# untitled.net
KiCad netlist of a schematic drawn in EAGLE
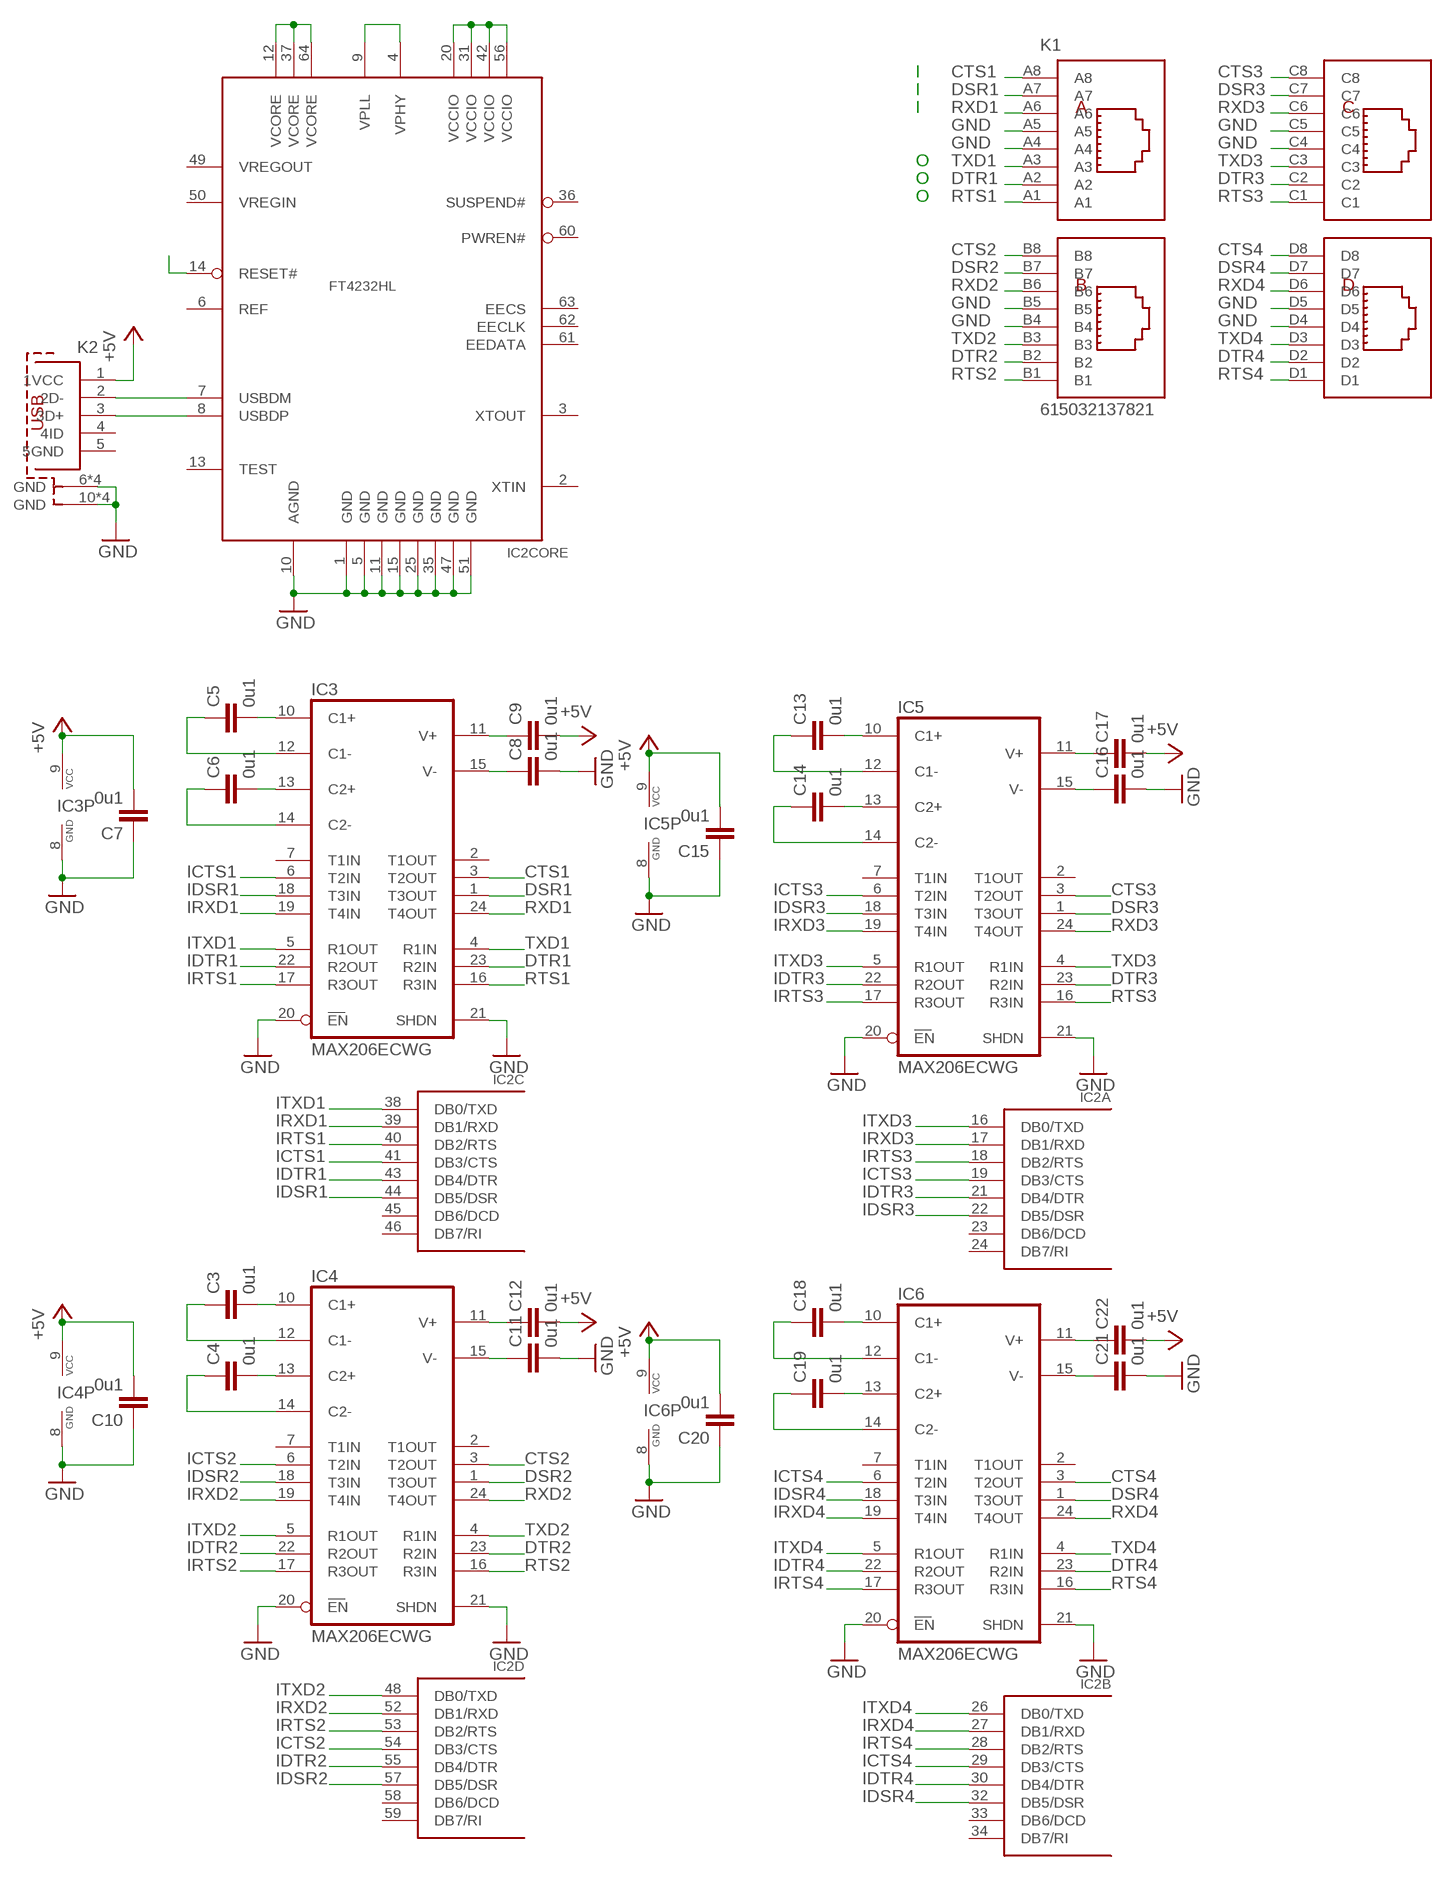
[diagram p0: schematic, sheet 1]

(export (version "E")
  (design (tool "Eeschema 10.0.6"))
  (components
    (comp (ref "C3")
      (value "0u1")
      (footprint "eagle-import:C0603")
      (libsource (lib "eagle-import") (part "C-EUC0603"))
    )
    (comp (ref "C4")
      (value "0u1")
      (footprint "eagle-import:C0603")
      (libsource (lib "eagle-import") (part "C-EUC0603"))
    )
    (comp (ref "C5")
      (value "0u1")
      (footprint "eagle-import:C0603")
      (libsource (lib "eagle-import") (part "C-EUC0603"))
    )
    (comp (ref "C6")
      (value "0u1")
      (footprint "eagle-import:C0603")
      (libsource (lib "eagle-import") (part "C-EUC0603"))
    )
    (comp (ref "C7")
      (value "0u1")
      (footprint "eagle-import:C0603")
      (libsource (lib "eagle-import") (part "C-EUC0603"))
    )
    (comp (ref "C8")
      (value "0u1")
      (footprint "eagle-import:C0603")
      (libsource (lib "eagle-import") (part "C-EUC0603"))
    )
    (comp (ref "C9")
      (value "0u1")
      (footprint "eagle-import:C0603")
      (libsource (lib "eagle-import") (part "C-EUC0603"))
    )
    (comp (ref "C10")
      (value "0u1")
      (footprint "eagle-import:C0603")
      (libsource (lib "eagle-import") (part "C-EUC0603"))
    )
    (comp (ref "C11")
      (value "0u1")
      (footprint "eagle-import:C0603")
      (libsource (lib "eagle-import") (part "C-EUC0603"))
    )
    (comp (ref "C12")
      (value "0u1")
      (footprint "eagle-import:C0603")
      (libsource (lib "eagle-import") (part "C-EUC0603"))
    )
    (comp (ref "C13")
      (value "0u1")
      (footprint "eagle-import:C0603")
      (libsource (lib "eagle-import") (part "C-EUC0603"))
    )
    (comp (ref "C14")
      (value "0u1")
      (footprint "eagle-import:C0603")
      (libsource (lib "eagle-import") (part "C-EUC0603"))
    )
    (comp (ref "C15")
      (value "0u1")
      (footprint "eagle-import:C0603")
      (libsource (lib "eagle-import") (part "C-EUC0603"))
    )
    (comp (ref "C16")
      (value "0u1")
      (footprint "eagle-import:C0603")
      (libsource (lib "eagle-import") (part "C-EUC0603"))
    )
    (comp (ref "C17")
      (value "0u1")
      (footprint "eagle-import:C0603")
      (libsource (lib "eagle-import") (part "C-EUC0603"))
    )
    (comp (ref "C18")
      (value "0u1")
      (footprint "eagle-import:C0603")
      (libsource (lib "eagle-import") (part "C-EUC0603"))
    )
    (comp (ref "C19")
      (value "0u1")
      (footprint "eagle-import:C0603")
      (libsource (lib "eagle-import") (part "C-EUC0603"))
    )
    (comp (ref "C20")
      (value "0u1")
      (footprint "eagle-import:C0603")
      (libsource (lib "eagle-import") (part "C-EUC0603"))
    )
    (comp (ref "C21")
      (value "0u1")
      (footprint "eagle-import:C0603")
      (libsource (lib "eagle-import") (part "C-EUC0603"))
    )
    (comp (ref "C22")
      (value "0u1")
      (footprint "eagle-import:C0603")
      (libsource (lib "eagle-import") (part "C-EUC0603"))
    )
    (comp (ref "IC2")
      (value "FT4232HL")
      (footprint "eagle-import:LQFP64")
      (libsource (lib "eagle-import") (part "FT4232HL"))
    )
    (comp (ref "IC3")
      (value "MAX206ECWG")
      (footprint "eagle-import:SO24L")
      (fields (field (name "MF") "MAXIM") (field (name "MPN") "MAX206ECWG+"))
      (libsource (lib "eagle-import") (part "MAX206ECWG"))
    )
    (comp (ref "IC4")
      (value "MAX206ECWG")
      (footprint "eagle-import:SO24L")
      (fields (field (name "MF") "MAXIM") (field (name "MPN") "MAX206ECWG+"))
      (libsource (lib "eagle-import") (part "MAX206ECWG"))
    )
    (comp (ref "IC5")
      (value "MAX206ECWG")
      (footprint "eagle-import:SO24L")
      (fields (field (name "MF") "MAXIM") (field (name "MPN") "MAX206ECWG+"))
      (libsource (lib "eagle-import") (part "MAX206ECWG"))
    )
    (comp (ref "IC6")
      (value "MAX206ECWG")
      (footprint "eagle-import:SO24L")
      (fields (field (name "MF") "MAXIM") (field (name "MPN") "MAX206ECWG+"))
      (libsource (lib "eagle-import") (part "MAX206ECWG"))
    )
    (comp (ref "K1")
      (value "615032137821")
      (footprint "eagle-import:615032137821")
      (libsource (lib "eagle-import") (part "615032137821"))
    )
    (comp (ref "K2")
      (value "629105150921")
      (footprint "eagle-import:629105150921")
      (libsource (lib "eagle-import") (part "629105150921"))
    )
  )
  (nets
    (net (code "1") (name "+5V") (class "Default")
      (node (ref "C10") (pin "2") (pinfunction "2_2") (pintype "passive"))
      (node (ref "C12") (pin "2") (pinfunction "2_2") (pintype "passive"))
      (node (ref "C15") (pin "2") (pinfunction "2_2") (pintype "passive"))
      (node (ref "C17") (pin "2") (pinfunction "2_2") (pintype "passive"))
      (node (ref "C20") (pin "2") (pinfunction "2_2") (pintype "passive"))
      (node (ref "C22") (pin "2") (pinfunction "2_2") (pintype "passive"))
      (node (ref "C7") (pin "2") (pinfunction "2_2") (pintype "passive"))
      (node (ref "C9") (pin "2") (pinfunction "2_2") (pintype "passive"))
      (node (ref "IC3") (pin "9") (pinfunction "VCC_9") (pintype "power_in"))
      (node (ref "IC4") (pin "9") (pinfunction "VCC_9") (pintype "power_in"))
      (node (ref "IC5") (pin "9") (pinfunction "VCC_9") (pintype "power_in"))
      (node (ref "IC6") (pin "9") (pinfunction "VCC_9") (pintype "power_in"))
      (node (ref "K2") (pin "1") (pinfunction "1VCC_1") (pintype "passive"))
    )
    (net (code "2") (name "/CTS1") (class "Default")
      (node (ref "IC3") (pin "3") (pinfunction "T2OUT_3") (pintype "output"))
      (node (ref "K1") (pin "A8") (pinfunction "A8_A8") (pintype "passive"))
    )
    (net (code "3") (name "/CTS2") (class "Default")
      (node (ref "IC4") (pin "3") (pinfunction "T2OUT_3") (pintype "output"))
      (node (ref "K1") (pin "B8") (pinfunction "B8_B8") (pintype "passive"))
    )
    (net (code "4") (name "/CTS3") (class "Default")
      (node (ref "IC5") (pin "3") (pinfunction "T2OUT_3") (pintype "output"))
      (node (ref "K1") (pin "C8") (pinfunction "C8_C8") (pintype "passive"))
    )
    (net (code "5") (name "/CTS4") (class "Default")
      (node (ref "IC6") (pin "3") (pinfunction "T2OUT_3") (pintype "output"))
      (node (ref "K1") (pin "D8") (pinfunction "D8_D8") (pintype "passive"))
    )
    (net (code "6") (name "/DSR1") (class "Default")
      (node (ref "IC3") (pin "1") (pinfunction "T3OUT_1") (pintype "output"))
      (node (ref "K1") (pin "A7") (pinfunction "A7_A7") (pintype "passive"))
    )
    (net (code "7") (name "/DSR2") (class "Default")
      (node (ref "IC4") (pin "1") (pinfunction "T3OUT_1") (pintype "output"))
      (node (ref "K1") (pin "B7") (pinfunction "B7_B7") (pintype "passive"))
    )
    (net (code "8") (name "/DSR3") (class "Default")
      (node (ref "IC5") (pin "1") (pinfunction "T3OUT_1") (pintype "output"))
      (node (ref "K1") (pin "C7") (pinfunction "C7_C7") (pintype "passive"))
    )
    (net (code "9") (name "/DSR4") (class "Default")
      (node (ref "IC6") (pin "1") (pinfunction "T3OUT_1") (pintype "output"))
      (node (ref "K1") (pin "D7") (pinfunction "D7_D7") (pintype "passive"))
    )
    (net (code "10") (name "/DTR1") (class "Default")
      (node (ref "IC3") (pin "23") (pinfunction "R2IN_23") (pintype "input"))
      (node (ref "K1") (pin "A2") (pinfunction "A2_A2") (pintype "passive"))
    )
    (net (code "11") (name "/DTR2") (class "Default")
      (node (ref "IC4") (pin "23") (pinfunction "R2IN_23") (pintype "input"))
      (node (ref "K1") (pin "B2") (pinfunction "B2_B2") (pintype "passive"))
    )
    (net (code "12") (name "/DTR3") (class "Default")
      (node (ref "IC5") (pin "23") (pinfunction "R2IN_23") (pintype "input"))
      (node (ref "K1") (pin "C2") (pinfunction "C2_C2") (pintype "passive"))
    )
    (net (code "13") (name "/DTR4") (class "Default")
      (node (ref "IC6") (pin "23") (pinfunction "R2IN_23") (pintype "input"))
      (node (ref "K1") (pin "D2") (pinfunction "D2_D2") (pintype "passive"))
    )
    (net (code "14") (name "/ICTS1") (class "Default")
      (node (ref "IC2") (pin "41") (pinfunction "DB3/CTS_41") (pintype "bidirectional"))
      (node (ref "IC3") (pin "6") (pinfunction "T2IN_6") (pintype "input"))
    )
    (net (code "15") (name "/ICTS2") (class "Default")
      (node (ref "IC2") (pin "54") (pinfunction "DB3/CTS_54") (pintype "bidirectional"))
      (node (ref "IC4") (pin "6") (pinfunction "T2IN_6") (pintype "input"))
    )
    (net (code "16") (name "/ICTS3") (class "Default")
      (node (ref "IC2") (pin "19") (pinfunction "DB3/CTS_19") (pintype "bidirectional"))
      (node (ref "IC5") (pin "6") (pinfunction "T2IN_6") (pintype "input"))
    )
    (net (code "17") (name "/ICTS4") (class "Default")
      (node (ref "IC2") (pin "29") (pinfunction "DB3/CTS_29") (pintype "bidirectional"))
      (node (ref "IC6") (pin "6") (pinfunction "T2IN_6") (pintype "input"))
    )
    (net (code "18") (name "/IDSR1") (class "Default")
      (node (ref "IC2") (pin "44") (pinfunction "DB5/DSR_44") (pintype "bidirectional"))
      (node (ref "IC3") (pin "18") (pinfunction "T3IN_18") (pintype "input"))
    )
    (net (code "19") (name "/IDSR2") (class "Default")
      (node (ref "IC2") (pin "57") (pinfunction "DB5/DSR_57") (pintype "bidirectional"))
      (node (ref "IC4") (pin "18") (pinfunction "T3IN_18") (pintype "input"))
    )
    (net (code "20") (name "/IDSR3") (class "Default")
      (node (ref "IC2") (pin "22") (pinfunction "DB5/DSR_22") (pintype "bidirectional"))
      (node (ref "IC5") (pin "18") (pinfunction "T3IN_18") (pintype "input"))
    )
    (net (code "21") (name "/IDSR4") (class "Default")
      (node (ref "IC2") (pin "32") (pinfunction "DB5/DSR_32") (pintype "bidirectional"))
      (node (ref "IC6") (pin "18") (pinfunction "T3IN_18") (pintype "input"))
    )
    (net (code "22") (name "/IDTR1") (class "Default")
      (node (ref "IC2") (pin "43") (pinfunction "DB4/DTR_43") (pintype "bidirectional"))
      (node (ref "IC3") (pin "22") (pinfunction "R2OUT_22") (pintype "output"))
    )
    (net (code "23") (name "/IDTR2") (class "Default")
      (node (ref "IC2") (pin "55") (pinfunction "DB4/DTR_55") (pintype "bidirectional"))
      (node (ref "IC4") (pin "22") (pinfunction "R2OUT_22") (pintype "output"))
    )
    (net (code "24") (name "/IDTR3") (class "Default")
      (node (ref "IC2") (pin "21") (pinfunction "DB4/DTR_21") (pintype "bidirectional"))
      (node (ref "IC5") (pin "22") (pinfunction "R2OUT_22") (pintype "output"))
    )
    (net (code "25") (name "/IDTR4") (class "Default")
      (node (ref "IC2") (pin "30") (pinfunction "DB4/DTR_30") (pintype "bidirectional"))
      (node (ref "IC6") (pin "22") (pinfunction "R2OUT_22") (pintype "output"))
    )
    (net (code "26") (name "/IRTS1") (class "Default")
      (node (ref "IC2") (pin "40") (pinfunction "DB2/RTS_40") (pintype "bidirectional"))
      (node (ref "IC3") (pin "17") (pinfunction "R3OUT_17") (pintype "output"))
    )
    (net (code "27") (name "/IRTS2") (class "Default")
      (node (ref "IC2") (pin "53") (pinfunction "DB2/RTS_53") (pintype "bidirectional"))
      (node (ref "IC4") (pin "17") (pinfunction "R3OUT_17") (pintype "output"))
    )
    (net (code "28") (name "/IRTS3") (class "Default")
      (node (ref "IC2") (pin "18") (pinfunction "DB2/RTS_18") (pintype "bidirectional"))
      (node (ref "IC5") (pin "17") (pinfunction "R3OUT_17") (pintype "output"))
    )
    (net (code "29") (name "/IRTS4") (class "Default")
      (node (ref "IC2") (pin "28") (pinfunction "DB2/RTS_28") (pintype "bidirectional"))
      (node (ref "IC6") (pin "17") (pinfunction "R3OUT_17") (pintype "output"))
    )
    (net (code "30") (name "/IRXD1") (class "Default")
      (node (ref "IC2") (pin "39") (pinfunction "DB1/RXD_39") (pintype "bidirectional"))
      (node (ref "IC3") (pin "19") (pinfunction "T4IN_19") (pintype "input"))
    )
    (net (code "31") (name "/IRXD2") (class "Default")
      (node (ref "IC2") (pin "52") (pinfunction "DB1/RXD_52") (pintype "bidirectional"))
      (node (ref "IC4") (pin "19") (pinfunction "T4IN_19") (pintype "input"))
    )
    (net (code "32") (name "/IRXD3") (class "Default")
      (node (ref "IC2") (pin "17") (pinfunction "DB1/RXD_17") (pintype "bidirectional"))
      (node (ref "IC5") (pin "19") (pinfunction "T4IN_19") (pintype "input"))
    )
    (net (code "33") (name "/IRXD4") (class "Default")
      (node (ref "IC2") (pin "27") (pinfunction "DB1/RXD_27") (pintype "bidirectional"))
      (node (ref "IC6") (pin "19") (pinfunction "T4IN_19") (pintype "input"))
    )
    (net (code "34") (name "/ITXD1") (class "Default")
      (node (ref "IC2") (pin "38") (pinfunction "DB0/TXD_38") (pintype "bidirectional"))
      (node (ref "IC3") (pin "5") (pinfunction "R1OUT_5") (pintype "output"))
    )
    (net (code "35") (name "/ITXD2") (class "Default")
      (node (ref "IC2") (pin "48") (pinfunction "DB0/TXD_48") (pintype "bidirectional"))
      (node (ref "IC4") (pin "5") (pinfunction "R1OUT_5") (pintype "output"))
    )
    (net (code "36") (name "/ITXD3") (class "Default")
      (node (ref "IC2") (pin "16") (pinfunction "DB0/TXD_16") (pintype "bidirectional"))
      (node (ref "IC5") (pin "5") (pinfunction "R1OUT_5") (pintype "output"))
    )
    (net (code "37") (name "/ITXD4") (class "Default")
      (node (ref "IC2") (pin "26") (pinfunction "DB0/TXD_26") (pintype "bidirectional"))
      (node (ref "IC6") (pin "5") (pinfunction "R1OUT_5") (pintype "output"))
    )
    (net (code "38") (name "/RTS1") (class "Default")
      (node (ref "IC3") (pin "16") (pinfunction "R3IN_16") (pintype "input"))
      (node (ref "K1") (pin "A1") (pinfunction "A1_A1") (pintype "passive"))
    )
    (net (code "39") (name "/RTS2") (class "Default")
      (node (ref "IC4") (pin "16") (pinfunction "R3IN_16") (pintype "input"))
      (node (ref "K1") (pin "B1") (pinfunction "B1_B1") (pintype "passive"))
    )
    (net (code "40") (name "/RTS3") (class "Default")
      (node (ref "IC5") (pin "16") (pinfunction "R3IN_16") (pintype "input"))
      (node (ref "K1") (pin "C1") (pinfunction "C1_C1") (pintype "passive"))
    )
    (net (code "41") (name "/RTS4") (class "Default")
      (node (ref "IC6") (pin "16") (pinfunction "R3IN_16") (pintype "input"))
      (node (ref "K1") (pin "D1") (pinfunction "D1_D1") (pintype "passive"))
    )
    (net (code "42") (name "/RXD1") (class "Default")
      (node (ref "IC3") (pin "24") (pinfunction "T4OUT_24") (pintype "output"))
      (node (ref "K1") (pin "A6") (pinfunction "A6_A6") (pintype "passive"))
    )
    (net (code "43") (name "/RXD2") (class "Default")
      (node (ref "IC4") (pin "24") (pinfunction "T4OUT_24") (pintype "output"))
      (node (ref "K1") (pin "B6") (pinfunction "B6_B6") (pintype "passive"))
    )
    (net (code "44") (name "/RXD3") (class "Default")
      (node (ref "IC5") (pin "24") (pinfunction "T4OUT_24") (pintype "output"))
      (node (ref "K1") (pin "C6") (pinfunction "C6_C6") (pintype "passive"))
    )
    (net (code "45") (name "/RXD4") (class "Default")
      (node (ref "IC6") (pin "24") (pinfunction "T4OUT_24") (pintype "output"))
      (node (ref "K1") (pin "D6") (pinfunction "D6_D6") (pintype "passive"))
    )
    (net (code "46") (name "/TXD1") (class "Default")
      (node (ref "IC3") (pin "4") (pinfunction "R1IN_4") (pintype "input"))
      (node (ref "K1") (pin "A3") (pinfunction "A3_A3") (pintype "passive"))
    )
    (net (code "47") (name "/TXD2") (class "Default")
      (node (ref "IC4") (pin "4") (pinfunction "R1IN_4") (pintype "input"))
      (node (ref "K1") (pin "B3") (pinfunction "B3_B3") (pintype "passive"))
    )
    (net (code "48") (name "/TXD3") (class "Default")
      (node (ref "IC5") (pin "4") (pinfunction "R1IN_4") (pintype "input"))
      (node (ref "K1") (pin "C3") (pinfunction "C3_C3") (pintype "passive"))
    )
    (net (code "49") (name "/TXD4") (class "Default")
      (node (ref "IC6") (pin "4") (pinfunction "R1IN_4") (pintype "input"))
      (node (ref "K1") (pin "D3") (pinfunction "D3_D3") (pintype "passive"))
    )
    (net (code "50") (name "GND") (class "Default")
      (node (ref "C10") (pin "1") (pinfunction "1_1") (pintype "passive"))
      (node (ref "C11") (pin "2") (pinfunction "2_2") (pintype "passive"))
      (node (ref "C15") (pin "1") (pinfunction "1_1") (pintype "passive"))
      (node (ref "C16") (pin "2") (pinfunction "2_2") (pintype "passive"))
      (node (ref "C20") (pin "1") (pinfunction "1_1") (pintype "passive"))
      (node (ref "C21") (pin "2") (pinfunction "2_2") (pintype "passive"))
      (node (ref "C7") (pin "1") (pinfunction "1_1") (pintype "passive"))
      (node (ref "C8") (pin "2") (pinfunction "2_2") (pintype "passive"))
      (node (ref "IC2") (pin "1") (pinfunction "GND_1") (pintype "power_in"))
      (node (ref "IC2") (pin "10") (pinfunction "AGND_10") (pintype "power_in"))
      (node (ref "IC2") (pin "11") (pinfunction "GND_11") (pintype "power_in"))
      (node (ref "IC2") (pin "15") (pinfunction "GND_15") (pintype "power_in"))
      (node (ref "IC2") (pin "25") (pinfunction "GND_25") (pintype "power_in"))
      (node (ref "IC2") (pin "35") (pinfunction "GND_35") (pintype "power_in"))
      (node (ref "IC2") (pin "47") (pinfunction "GND_47") (pintype "power_in"))
      (node (ref "IC2") (pin "5") (pinfunction "GND_5") (pintype "power_in"))
      (node (ref "IC2") (pin "51") (pinfunction "GND_51") (pintype "power_in"))
      (node (ref "IC3") (pin "20") (pinfunction "EN_20") (pintype "passive"))
      (node (ref "IC3") (pin "21") (pinfunction "SHDN_21") (pintype "passive"))
      (node (ref "IC3") (pin "8") (pinfunction "GND_8") (pintype "power_in"))
      (node (ref "IC4") (pin "20") (pinfunction "EN_20") (pintype "passive"))
      (node (ref "IC4") (pin "21") (pinfunction "SHDN_21") (pintype "passive"))
      (node (ref "IC4") (pin "8") (pinfunction "GND_8") (pintype "power_in"))
      (node (ref "IC5") (pin "20") (pinfunction "EN_20") (pintype "passive"))
      (node (ref "IC5") (pin "21") (pinfunction "SHDN_21") (pintype "passive"))
      (node (ref "IC5") (pin "8") (pinfunction "GND_8") (pintype "power_in"))
      (node (ref "IC6") (pin "20") (pinfunction "EN_20") (pintype "passive"))
      (node (ref "IC6") (pin "21") (pinfunction "SHDN_21") (pintype "passive"))
      (node (ref "IC6") (pin "8") (pinfunction "GND_8") (pintype "power_in"))
      (node (ref "K1") (pin "A4") (pinfunction "A4_A4") (pintype "passive"))
      (node (ref "K1") (pin "A5") (pinfunction "A5_A5") (pintype "passive"))
      (node (ref "K1") (pin "B4") (pinfunction "B4_B4") (pintype "passive"))
      (node (ref "K1") (pin "B5") (pinfunction "B5_B5") (pintype "passive"))
      (node (ref "K1") (pin "C4") (pinfunction "C4_C4") (pintype "passive"))
      (node (ref "K1") (pin "C5") (pinfunction "C5_C5") (pintype "passive"))
      (node (ref "K1") (pin "D4") (pinfunction "D4_D4") (pintype "passive"))
      (node (ref "K1") (pin "D5") (pinfunction "D5_D5") (pintype "passive"))
      (node (ref "K2") (pin "10") (pinfunction "GND_10") (pintype "bidirectional"))
      (node (ref "K2") (pin "11") (pinfunction "GND_11") (pintype "bidirectional"))
      (node (ref "K2") (pin "12") (pinfunction "GND_12") (pintype "bidirectional"))
      (node (ref "K2") (pin "13") (pinfunction "GND_13") (pintype "bidirectional"))
      (node (ref "K2") (pin "6") (pinfunction "GND_6") (pintype "bidirectional"))
      (node (ref "K2") (pin "7") (pinfunction "GND_7") (pintype "bidirectional"))
      (node (ref "K2") (pin "8") (pinfunction "GND_8") (pintype "bidirectional"))
      (node (ref "K2") (pin "9") (pinfunction "GND_9") (pintype "bidirectional"))
    )
    (net (code "51") (name "Net-(IC2D-USBDM)") (class "Default")
      (node (ref "IC2") (pin "7") (pinfunction "USBDM_7") (pintype "input"))
      (node (ref "K2") (pin "2") (pinfunction "2D-_2") (pintype "passive"))
    )
    (net (code "52") (name "Net-(IC2D-USBDP)") (class "Default")
      (node (ref "IC2") (pin "8") (pinfunction "USBDP_8") (pintype "input"))
      (node (ref "K2") (pin "3") (pinfunction "3D+_3") (pintype "passive"))
    )
    (net (code "53") (name "Net-(IC2D-VCCIO-Pad20)") (class "Default")
      (node (ref "IC2") (pin "20") (pinfunction "VCCIO_20") (pintype "power_in"))
      (node (ref "IC2") (pin "31") (pinfunction "VCCIO_31") (pintype "power_in"))
      (node (ref "IC2") (pin "42") (pinfunction "VCCIO_42") (pintype "power_in"))
      (node (ref "IC2") (pin "56") (pinfunction "VCCIO_56") (pintype "power_in"))
    )
    (net (code "54") (name "Net-(IC2D-VCORE-Pad12)") (class "Default")
      (node (ref "IC2") (pin "12") (pinfunction "VCORE_12") (pintype "power_in"))
      (node (ref "IC2") (pin "37") (pinfunction "VCORE_37") (pintype "power_in"))
      (node (ref "IC2") (pin "64") (pinfunction "VCORE_64") (pintype "power_in"))
    )
    (net (code "55") (name "Net-(IC2D-VPHY)") (class "Default")
      (node (ref "IC2") (pin "4") (pinfunction "VPHY_4") (pintype "power_in"))
      (node (ref "IC2") (pin "9") (pinfunction "VPLL_9") (pintype "power_in"))
    )
    (net (code "56") (name "Net-(IC3A-C1+)") (class "Default")
      (node (ref "C5") (pin "2") (pinfunction "2_2") (pintype "passive"))
      (node (ref "IC3") (pin "10") (pinfunction "C1+_10") (pintype "bidirectional"))
    )
    (net (code "57") (name "Net-(IC3A-C1-)") (class "Default")
      (node (ref "C5") (pin "1") (pinfunction "1_1") (pintype "passive"))
      (node (ref "IC3") (pin "12") (pinfunction "C1-_12") (pintype "bidirectional"))
    )
    (net (code "58") (name "Net-(IC3A-C2+)") (class "Default")
      (node (ref "C6") (pin "2") (pinfunction "2_2") (pintype "passive"))
      (node (ref "IC3") (pin "13") (pinfunction "C2+_13") (pintype "bidirectional"))
    )
    (net (code "59") (name "Net-(IC3A-C2-)") (class "Default")
      (node (ref "C6") (pin "1") (pinfunction "1_1") (pintype "passive"))
      (node (ref "IC3") (pin "14") (pinfunction "C2-_14") (pintype "bidirectional"))
    )
    (net (code "60") (name "Net-(IC3A-V+)") (class "Default")
      (node (ref "C9") (pin "1") (pinfunction "1_1") (pintype "passive"))
      (node (ref "IC3") (pin "11") (pinfunction "V+_11") (pintype "bidirectional"))
    )
    (net (code "61") (name "Net-(IC3A-V-)") (class "Default")
      (node (ref "C8") (pin "1") (pinfunction "1_1") (pintype "passive"))
      (node (ref "IC3") (pin "15") (pinfunction "V-_15") (pintype "bidirectional"))
    )
    (net (code "62") (name "Net-(IC4A-C1+)") (class "Default")
      (node (ref "C3") (pin "2") (pinfunction "2_2") (pintype "passive"))
      (node (ref "IC4") (pin "10") (pinfunction "C1+_10") (pintype "bidirectional"))
    )
    (net (code "63") (name "Net-(IC4A-C1-)") (class "Default")
      (node (ref "C3") (pin "1") (pinfunction "1_1") (pintype "passive"))
      (node (ref "IC4") (pin "12") (pinfunction "C1-_12") (pintype "bidirectional"))
    )
    (net (code "64") (name "Net-(IC4A-C2+)") (class "Default")
      (node (ref "C4") (pin "2") (pinfunction "2_2") (pintype "passive"))
      (node (ref "IC4") (pin "13") (pinfunction "C2+_13") (pintype "bidirectional"))
    )
    (net (code "65") (name "Net-(IC4A-C2-)") (class "Default")
      (node (ref "C4") (pin "1") (pinfunction "1_1") (pintype "passive"))
      (node (ref "IC4") (pin "14") (pinfunction "C2-_14") (pintype "bidirectional"))
    )
    (net (code "66") (name "Net-(IC4A-V+)") (class "Default")
      (node (ref "C12") (pin "1") (pinfunction "1_1") (pintype "passive"))
      (node (ref "IC4") (pin "11") (pinfunction "V+_11") (pintype "bidirectional"))
    )
    (net (code "67") (name "Net-(IC4A-V-)") (class "Default")
      (node (ref "C11") (pin "1") (pinfunction "1_1") (pintype "passive"))
      (node (ref "IC4") (pin "15") (pinfunction "V-_15") (pintype "bidirectional"))
    )
    (net (code "68") (name "Net-(IC5A-C1+)") (class "Default")
      (node (ref "C13") (pin "2") (pinfunction "2_2") (pintype "passive"))
      (node (ref "IC5") (pin "10") (pinfunction "C1+_10") (pintype "bidirectional"))
    )
    (net (code "69") (name "Net-(IC5A-C1-)") (class "Default")
      (node (ref "C13") (pin "1") (pinfunction "1_1") (pintype "passive"))
      (node (ref "IC5") (pin "12") (pinfunction "C1-_12") (pintype "bidirectional"))
    )
    (net (code "70") (name "Net-(IC5A-C2+)") (class "Default")
      (node (ref "C14") (pin "2") (pinfunction "2_2") (pintype "passive"))
      (node (ref "IC5") (pin "13") (pinfunction "C2+_13") (pintype "bidirectional"))
    )
    (net (code "71") (name "Net-(IC5A-C2-)") (class "Default")
      (node (ref "C14") (pin "1") (pinfunction "1_1") (pintype "passive"))
      (node (ref "IC5") (pin "14") (pinfunction "C2-_14") (pintype "bidirectional"))
    )
    (net (code "72") (name "Net-(IC5A-V+)") (class "Default")
      (node (ref "C17") (pin "1") (pinfunction "1_1") (pintype "passive"))
      (node (ref "IC5") (pin "11") (pinfunction "V+_11") (pintype "bidirectional"))
    )
    (net (code "73") (name "Net-(IC5A-V-)") (class "Default")
      (node (ref "C16") (pin "1") (pinfunction "1_1") (pintype "passive"))
      (node (ref "IC5") (pin "15") (pinfunction "V-_15") (pintype "bidirectional"))
    )
    (net (code "74") (name "Net-(IC6A-C1+)") (class "Default")
      (node (ref "C18") (pin "2") (pinfunction "2_2") (pintype "passive"))
      (node (ref "IC6") (pin "10") (pinfunction "C1+_10") (pintype "bidirectional"))
    )
    (net (code "75") (name "Net-(IC6A-C1-)") (class "Default")
      (node (ref "C18") (pin "1") (pinfunction "1_1") (pintype "passive"))
      (node (ref "IC6") (pin "12") (pinfunction "C1-_12") (pintype "bidirectional"))
    )
    (net (code "76") (name "Net-(IC6A-C2+)") (class "Default")
      (node (ref "C19") (pin "2") (pinfunction "2_2") (pintype "passive"))
      (node (ref "IC6") (pin "13") (pinfunction "C2+_13") (pintype "bidirectional"))
    )
    (net (code "77") (name "Net-(IC6A-C2-)") (class "Default")
      (node (ref "C19") (pin "1") (pinfunction "1_1") (pintype "passive"))
      (node (ref "IC6") (pin "14") (pinfunction "C2-_14") (pintype "bidirectional"))
    )
    (net (code "78") (name "Net-(IC6A-V+)") (class "Default")
      (node (ref "C22") (pin "1") (pinfunction "1_1") (pintype "passive"))
      (node (ref "IC6") (pin "11") (pinfunction "V+_11") (pintype "bidirectional"))
    )
    (net (code "79") (name "Net-(IC6A-V-)") (class "Default")
      (node (ref "C21") (pin "1") (pinfunction "1_1") (pintype "passive"))
      (node (ref "IC6") (pin "15") (pinfunction "V-_15") (pintype "bidirectional"))
    )
    (net (code "80") (name "unconnected-(IC2A-DB6{slash}DCD-Pad23)") (class "Default")
      (node (ref "IC2") (pin "23") (pinfunction "DB6/DCD_23") (pintype "bidirectional"))
    )
    (net (code "81") (name "unconnected-(IC2A-DB7{slash}RI-Pad24)") (class "Default")
      (node (ref "IC2") (pin "24") (pinfunction "DB7/RI_24") (pintype "bidirectional"))
    )
    (net (code "82") (name "unconnected-(IC2B-DB6{slash}DCD-Pad33)") (class "Default")
      (node (ref "IC2") (pin "33") (pinfunction "DB6/DCD_33") (pintype "bidirectional"))
    )
    (net (code "83") (name "unconnected-(IC2B-DB7{slash}RI-Pad34)") (class "Default")
      (node (ref "IC2") (pin "34") (pinfunction "DB7/RI_34") (pintype "bidirectional"))
    )
    (net (code "84") (name "unconnected-(IC2C-DB6{slash}DCD-Pad45)") (class "Default")
      (node (ref "IC2") (pin "45") (pinfunction "DB6/DCD_45") (pintype "bidirectional"))
    )
    (net (code "85") (name "unconnected-(IC2C-DB7{slash}RI-Pad46)") (class "Default")
      (node (ref "IC2") (pin "46") (pinfunction "DB7/RI_46") (pintype "bidirectional"))
    )
    (net (code "86") (name "unconnected-(IC2D-EECLK-Pad62)") (class "Default")
      (node (ref "IC2") (pin "62") (pinfunction "EECLK_62") (pintype "output"))
    )
    (net (code "87") (name "unconnected-(IC2D-EECS-Pad63)") (class "Default")
      (node (ref "IC2") (pin "63") (pinfunction "EECS_63") (pintype "bidirectional"))
    )
    (net (code "88") (name "unconnected-(IC2D-EEDATA-Pad61)") (class "Default")
      (node (ref "IC2") (pin "61") (pinfunction "EEDATA_61") (pintype "bidirectional"))
    )
    (net (code "89") (name "unconnected-(IC2D-PWREN#-Pad60)") (class "Default")
      (node (ref "IC2") (pin "60") (pinfunction "PWREN#_60") (pintype "output"))
    )
    (net (code "90") (name "unconnected-(IC2D-REF-Pad6)") (class "Default")
      (node (ref "IC2") (pin "6") (pinfunction "REF_6") (pintype "input"))
    )
    (net (code "91") (name "unconnected-(IC2D-RESET#-Pad14)") (class "Default")
      (node (ref "IC2") (pin "14") (pinfunction "RESET#_14") (pintype "input"))
    )
    (net (code "92") (name "unconnected-(IC2D-SUSPEND#-Pad36)") (class "Default")
      (node (ref "IC2") (pin "36") (pinfunction "SUSPEND#_36") (pintype "output"))
    )
    (net (code "93") (name "unconnected-(IC2D-TEST-Pad13)") (class "Default")
      (node (ref "IC2") (pin "13") (pinfunction "TEST_13") (pintype "input"))
    )
    (net (code "94") (name "unconnected-(IC2D-VREGIN-Pad50)") (class "Default")
      (node (ref "IC2") (pin "50") (pinfunction "VREGIN_50") (pintype "bidirectional"))
    )
    (net (code "95") (name "unconnected-(IC2D-VREGOUT-Pad49)") (class "Default")
      (node (ref "IC2") (pin "49") (pinfunction "VREGOUT_49") (pintype "output"))
    )
    (net (code "96") (name "unconnected-(IC2D-XTIN-Pad2)") (class "Default")
      (node (ref "IC2") (pin "2") (pinfunction "XTIN_2") (pintype "input"))
    )
    (net (code "97") (name "unconnected-(IC2D-XTOUT-Pad3)") (class "Default")
      (node (ref "IC2") (pin "3") (pinfunction "XTOUT_3") (pintype "output"))
    )
    (net (code "98") (name "unconnected-(IC2E-DB6{slash}DCD-Pad58)") (class "Default")
      (node (ref "IC2") (pin "58") (pinfunction "DB6/DCD_58") (pintype "bidirectional"))
    )
    (net (code "99") (name "unconnected-(IC2E-DB7{slash}RI-Pad59)") (class "Default")
      (node (ref "IC2") (pin "59") (pinfunction "DB7/RI_59") (pintype "bidirectional"))
    )
    (net (code "100") (name "unconnected-(IC3A-T1IN-Pad7)") (class "Default")
      (node (ref "IC3") (pin "7") (pinfunction "T1IN_7") (pintype "input"))
    )
    (net (code "101") (name "unconnected-(IC3A-T1OUT-Pad2)") (class "Default")
      (node (ref "IC3") (pin "2") (pinfunction "T1OUT_2") (pintype "output"))
    )
    (net (code "102") (name "unconnected-(IC4A-T1IN-Pad7)") (class "Default")
      (node (ref "IC4") (pin "7") (pinfunction "T1IN_7") (pintype "input"))
    )
    (net (code "103") (name "unconnected-(IC4A-T1OUT-Pad2)") (class "Default")
      (node (ref "IC4") (pin "2") (pinfunction "T1OUT_2") (pintype "output"))
    )
    (net (code "104") (name "unconnected-(IC5A-T1IN-Pad7)") (class "Default")
      (node (ref "IC5") (pin "7") (pinfunction "T1IN_7") (pintype "input"))
    )
    (net (code "105") (name "unconnected-(IC5A-T1OUT-Pad2)") (class "Default")
      (node (ref "IC5") (pin "2") (pinfunction "T1OUT_2") (pintype "output"))
    )
    (net (code "106") (name "unconnected-(IC6A-T1IN-Pad7)") (class "Default")
      (node (ref "IC6") (pin "7") (pinfunction "T1IN_7") (pintype "input"))
    )
    (net (code "107") (name "unconnected-(IC6A-T1OUT-Pad2)") (class "Default")
      (node (ref "IC6") (pin "2") (pinfunction "T1OUT_2") (pintype "output"))
    )
    (net (code "108") (name "unconnected-(K2-4ID-Pad4)") (class "Default")
      (node (ref "K2") (pin "4") (pinfunction "4ID_4") (pintype "passive"))
    )
    (net (code "109") (name "unconnected-(K2-5GND-Pad5)") (class "Default")
      (node (ref "K2") (pin "5") (pinfunction "5GND_5") (pintype "passive"))
    )
  )
)
